# KGGR_MV.net
KiCad netlist of a schematic drawn in EAGLE
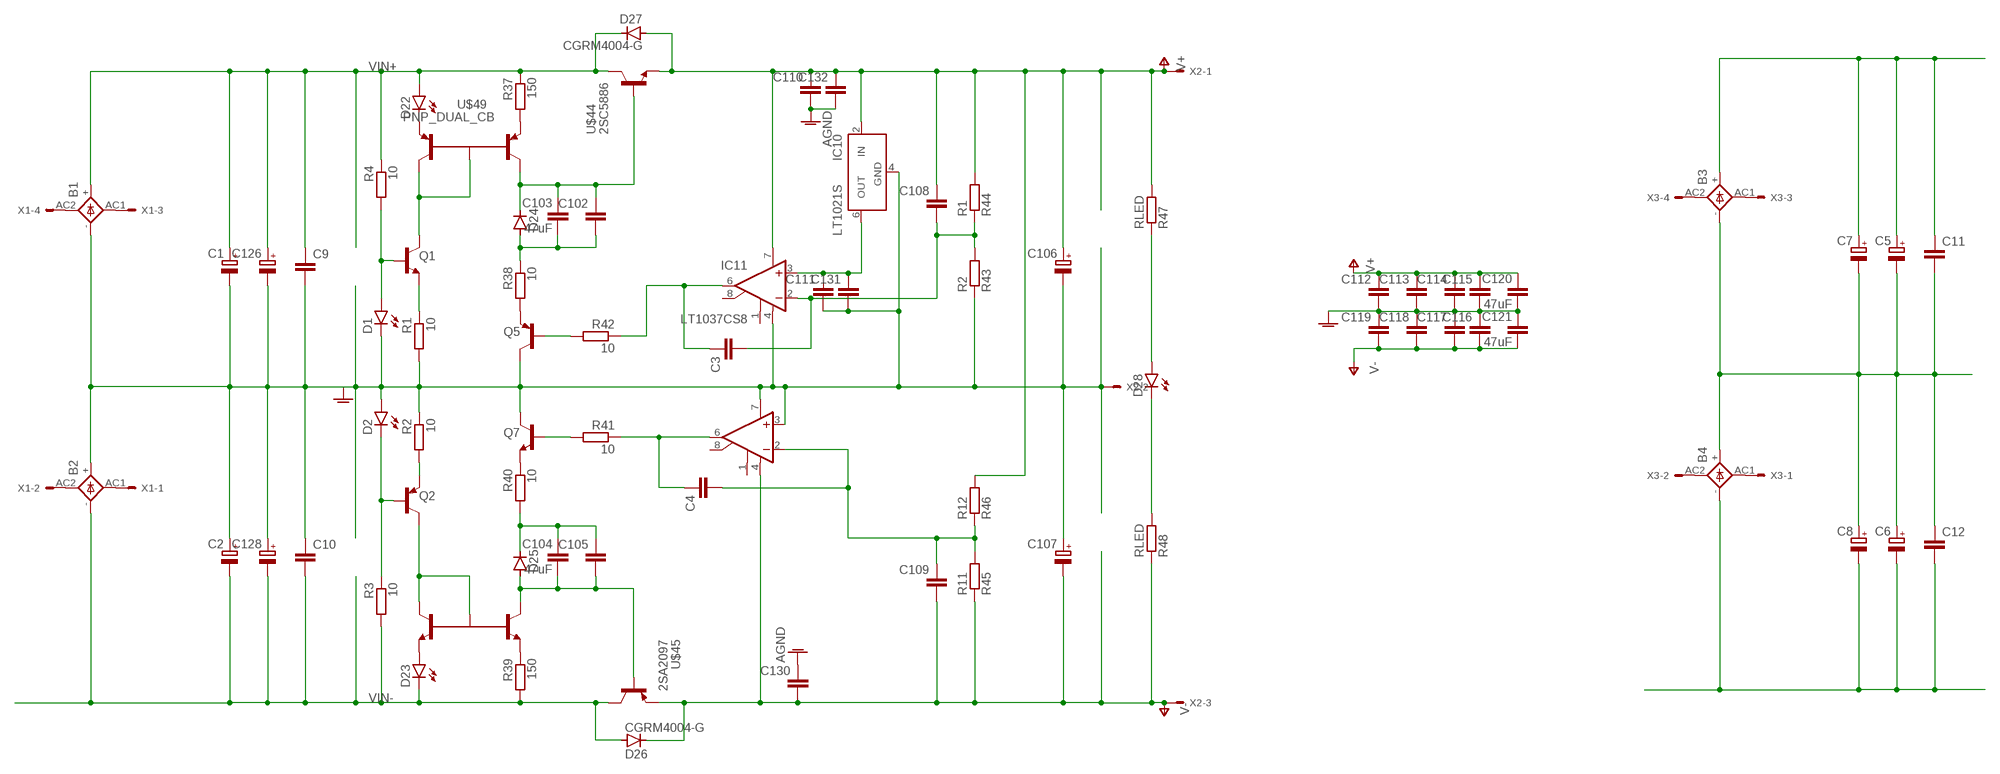
[diagram p0: schematic, sheet 1]

(export (version "E")
  (design (tool "Eeschema 10.0.6"))
  (components
    (comp (ref "B1")
      (value "GBU4")
      (footprint "eagle-import:GBU4S")
      (libsource (lib "eagle-import") (part "GBU4"))
    )
    (comp (ref "B2")
      (value "GBU4")
      (footprint "eagle-import:GBU4S")
      (libsource (lib "eagle-import") (part "GBU4"))
    )
    (comp (ref "B3")
      (value "GBU4")
      (footprint "eagle-import:GBU4S")
      (libsource (lib "eagle-import") (part "GBU4"))
    )
    (comp (ref "B4")
      (value "GBU4")
      (footprint "eagle-import:GBU4S")
      (libsource (lib "eagle-import") (part "GBU4"))
    )
    (comp (ref "C1")
      (value "CPOL-EUE7.5-18")
      (footprint "eagle-import:E7,5-18")
      (libsource (lib "eagle-import") (part "CPOL-EUE7.5-18"))
    )
    (comp (ref "C2")
      (value "CPOL-EUE7.5-18")
      (footprint "eagle-import:E7,5-18")
      (libsource (lib "eagle-import") (part "CPOL-EUE7.5-18"))
    )
    (comp (ref "C3")
      (value "C-EUC0805")
      (footprint "eagle-import:C0805")
      (libsource (lib "eagle-import") (part "C-EUC0805"))
    )
    (comp (ref "C4")
      (value "C-EUC0805")
      (footprint "eagle-import:C0805")
      (libsource (lib "eagle-import") (part "C-EUC0805"))
    )
    (comp (ref "C5")
      (value "CPOL-EUE10-35")
      (footprint "eagle-import:EB35D")
      (libsource (lib "eagle-import") (part "CPOL-EUE10-35"))
    )
    (comp (ref "C6")
      (value "CPOL-EUE10-35")
      (footprint "eagle-import:EB35D")
      (libsource (lib "eagle-import") (part "CPOL-EUE10-35"))
    )
    (comp (ref "C7")
      (value "CPOL-EUE10-35")
      (footprint "eagle-import:EB35D")
      (libsource (lib "eagle-import") (part "CPOL-EUE10-35"))
    )
    (comp (ref "C8")
      (value "CPOL-EUE10-35")
      (footprint "eagle-import:EB35D")
      (libsource (lib "eagle-import") (part "CPOL-EUE10-35"))
    )
    (comp (ref "C9")
      (value "C-EU050-050X075")
      (footprint "eagle-import:C050-050X075")
      (libsource (lib "eagle-import") (part "C-EU050-050X075"))
    )
    (comp (ref "C10")
      (value "C-EU050-050X075")
      (footprint "eagle-import:C050-050X075")
      (libsource (lib "eagle-import") (part "C-EU050-050X075"))
    )
    (comp (ref "C11")
      (value "C-EU050-050X075")
      (footprint "eagle-import:C050-050X075")
      (libsource (lib "eagle-import") (part "C-EU050-050X075"))
    )
    (comp (ref "C12")
      (value "C-EU050-050X075")
      (footprint "eagle-import:C050-050X075")
      (libsource (lib "eagle-import") (part "C-EU050-050X075"))
    )
    (comp (ref "C102")
      (value "C-EUC0805")
      (footprint "eagle-import:C0805")
      (libsource (lib "eagle-import") (part "C-EUC0805"))
    )
    (comp (ref "C103")
      (value "47uF")
      (footprint "eagle-import:C1206")
      (libsource (lib "eagle-import") (part "C-EUC1206"))
    )
    (comp (ref "C104")
      (value "47uF")
      (footprint "eagle-import:C1206")
      (libsource (lib "eagle-import") (part "C-EUC1206"))
    )
    (comp (ref "C105")
      (value "C-EUC0805")
      (footprint "eagle-import:C0805")
      (libsource (lib "eagle-import") (part "C-EUC0805"))
    )
    (comp (ref "C106")
      (value "CPOL-EUE5-10.5")
      (footprint "eagle-import:E5-10,5")
      (libsource (lib "eagle-import") (part "CPOL-EUE5-10.5"))
    )
    (comp (ref "C107")
      (value "CPOL-EUE5-10.5")
      (footprint "eagle-import:E5-10,5")
      (libsource (lib "eagle-import") (part "CPOL-EUE5-10.5"))
    )
    (comp (ref "C108")
      (value "C-EUC0805")
      (footprint "eagle-import:C0805")
      (libsource (lib "eagle-import") (part "C-EUC0805"))
    )
    (comp (ref "C109")
      (value "C-EUC0805")
      (footprint "eagle-import:C0805")
      (libsource (lib "eagle-import") (part "C-EUC0805"))
    )
    (comp (ref "C110")
      (value "C-EUC0805")
      (footprint "eagle-import:C0805")
      (libsource (lib "eagle-import") (part "C-EUC0805"))
    )
    (comp (ref "C111")
      (value "C-EUC0805")
      (footprint "eagle-import:C0805")
      (libsource (lib "eagle-import") (part "C-EUC0805"))
    )
    (comp (ref "C112")
      (value "C-EUC0805")
      (footprint "eagle-import:C0805")
      (libsource (lib "eagle-import") (part "C-EUC0805"))
    )
    (comp (ref "C113")
      (value "C-EUC0805")
      (footprint "eagle-import:C0805")
      (libsource (lib "eagle-import") (part "C-EUC0805"))
    )
    (comp (ref "C114")
      (value "C-EUC0805")
      (footprint "eagle-import:C0805")
      (libsource (lib "eagle-import") (part "C-EUC0805"))
    )
    (comp (ref "C115")
      (value "C-EUC0805")
      (footprint "eagle-import:C0805")
      (libsource (lib "eagle-import") (part "C-EUC0805"))
    )
    (comp (ref "C116")
      (value "C-EUC0805")
      (footprint "eagle-import:C0805")
      (libsource (lib "eagle-import") (part "C-EUC0805"))
    )
    (comp (ref "C117")
      (value "C-EUC0805")
      (footprint "eagle-import:C0805")
      (libsource (lib "eagle-import") (part "C-EUC0805"))
    )
    (comp (ref "C118")
      (value "C-EUC0805")
      (footprint "eagle-import:C0805")
      (libsource (lib "eagle-import") (part "C-EUC0805"))
    )
    (comp (ref "C119")
      (value "C-EUC0805")
      (footprint "eagle-import:C0805")
      (libsource (lib "eagle-import") (part "C-EUC0805"))
    )
    (comp (ref "C120")
      (value "47uF")
      (footprint "eagle-import:C1206")
      (libsource (lib "eagle-import") (part "C-EUC1206"))
    )
    (comp (ref "C121")
      (value "47uF")
      (footprint "eagle-import:C1206")
      (libsource (lib "eagle-import") (part "C-EUC1206"))
    )
    (comp (ref "C126")
      (value "CPOL-EUE7.5-18")
      (footprint "eagle-import:E7,5-18")
      (libsource (lib "eagle-import") (part "CPOL-EUE7.5-18"))
    )
    (comp (ref "C128")
      (value "CPOL-EUE7.5-18")
      (footprint "eagle-import:E7,5-18")
      (libsource (lib "eagle-import") (part "CPOL-EUE7.5-18"))
    )
    (comp (ref "C130")
      (value "C-EUC0805")
      (footprint "eagle-import:C0805")
      (libsource (lib "eagle-import") (part "C-EUC0805"))
    )
    (comp (ref "C131")
      (value "C-EUC0805")
      (footprint "eagle-import:C0805")
      (libsource (lib "eagle-import") (part "C-EUC0805"))
    )
    (comp (ref "C132")
      (value "C-EUC0805")
      (footprint "eagle-import:C0805")
      (libsource (lib "eagle-import") (part "C-EUC0805"))
    )
    (comp (ref "D1")
      (value "LEDVWV1206")
      (footprint "eagle-import:LED_SML1206")
      (libsource (lib "eagle-import") (part "LEDVWV1206"))
    )
    (comp (ref "D2")
      (value "LEDVWV1206")
      (footprint "eagle-import:LED_SML1206")
      (libsource (lib "eagle-import") (part "LEDVWV1206"))
    )
    (comp (ref "D22")
      (value "LEDVWV1206")
      (footprint "eagle-import:LED_SML1206")
      (libsource (lib "eagle-import") (part "LEDVWV1206"))
    )
    (comp (ref "D23")
      (value "LEDVWV1206")
      (footprint "eagle-import:LED_SML1206")
      (libsource (lib "eagle-import") (part "LEDVWV1206"))
    )
    (comp (ref "D24")
      (value "TZMC10")
      (footprint "eagle-import:SOD80C")
      (libsource (lib "eagle-import") (part "DIODE-SOD80C"))
    )
    (comp (ref "D25")
      (value "TZAMC10")
      (footprint "eagle-import:SOD80C")
      (libsource (lib "eagle-import") (part "DIODE-SOD80C"))
    )
    (comp (ref "D26")
      (value "CGRM4004-G")
      (footprint "eagle-import:SOD-123_MINI-SMA")
      (libsource (lib "eagle-import") (part "CGRM400-G4"))
    )
    (comp (ref "D27")
      (value "CGRM4004-G")
      (footprint "eagle-import:SOD-123_MINI-SMA")
      (libsource (lib "eagle-import") (part "CGRM400-G4"))
    )
    (comp (ref "D28")
      (value "LEDVWV1206")
      (footprint "eagle-import:LED_SML1206")
      (libsource (lib "eagle-import") (part "LEDVWV1206"))
    )
    (comp (ref "IC10")
      (value "LT1021S")
      (footprint "eagle-import:SOIC8")
      (fields (field (name "MPN") "LT1021DCS8-10#PBF"))
      (libsource (lib "eagle-import") (part "LT1021S"))
    )
    (comp (ref "IC11")
      (value "LT1037CS8")
      (footprint "eagle-import:SOIC8")
      (libsource (lib "eagle-import") (part "LT10S837C"))
    )
    (comp (ref "IC12")
      (value "LT1037CS8")
      (footprint "eagle-import:SOIC8")
      (libsource (lib "eagle-import") (part "LT10S837C"))
    )
    (comp (ref "Q1")
      (value "TRANSISTOR_BC847CLT1-NPN-SOT23-BEC")
      (footprint "eagle-import:TRANSISTOR_SOT23-BEC")
      (libsource (lib "eagle-import") (part "TRANSISTOR_-NPN-SOT23-BECBC847CLT1"))
    )
    (comp (ref "Q2")
      (value "TRANSISTOR_BC857C-PNP-SOT23-BEC")
      (footprint "eagle-import:TRANSISTOR_SOT23-BEC")
      (libsource (lib "eagle-import") (part "TRANSISTOR_-PNP-SOT23-BECBC857C"))
    )
    (comp (ref "Q5")
      (value "TRANSISTOR_BC857C-PNP-SOT23-BEC")
      (footprint "eagle-import:TRANSISTOR_SOT23-BEC")
      (libsource (lib "eagle-import") (part "TRANSISTOR_-PNP-SOT23-BECBC857C"))
    )
    (comp (ref "Q7")
      (value "TRANSISTOR_BC847CLT1-NPN-SOT23-BEC")
      (footprint "eagle-import:TRANSISTOR_SOT23-BEC")
      (libsource (lib "eagle-import") (part "TRANSISTOR_-NPN-SOT23-BECBC847CLT1"))
    )
    (comp (ref "R1")
      (value "10")
      (footprint "eagle-import:MINI_MELF-0204W")
      (libsource (lib "eagle-import") (part "R-EU_MELF0204W"))
    )
    (comp (ref "R2")
      (value "10")
      (footprint "eagle-import:MINI_MELF-0204W")
      (libsource (lib "eagle-import") (part "R-EU_MELF0204W"))
    )
    (comp (ref "R3")
      (value "10")
      (footprint "eagle-import:MINI_MELF-0204W")
      (libsource (lib "eagle-import") (part "R-EU_MELF0204W"))
    )
    (comp (ref "R4")
      (value "10")
      (footprint "eagle-import:MINI_MELF-0204W")
      (libsource (lib "eagle-import") (part "R-EU_MELF0204W"))
    )
    (comp (ref "R37")
      (value "150")
      (footprint "eagle-import:MINI_MELF-0204W")
      (libsource (lib "eagle-import") (part "R-EU_MELF0204W"))
    )
    (comp (ref "R38")
      (value "10")
      (footprint "eagle-import:MINI_MELF-0204W")
      (libsource (lib "eagle-import") (part "R-EU_MELF0204W"))
    )
    (comp (ref "R39")
      (value "150")
      (footprint "eagle-import:MINI_MELF-0204W")
      (libsource (lib "eagle-import") (part "R-EU_MELF0204W"))
    )
    (comp (ref "R40")
      (value "10")
      (footprint "eagle-import:MINI_MELF-0204W")
      (libsource (lib "eagle-import") (part "R-EU_MELF0204W"))
    )
    (comp (ref "R41")
      (value "10")
      (footprint "eagle-import:MINI_MELF-0204W")
      (libsource (lib "eagle-import") (part "R-EU_MELF0204W"))
    )
    (comp (ref "R42")
      (value "10")
      (footprint "eagle-import:MINI_MELF-0204W")
      (libsource (lib "eagle-import") (part "R-EU_MELF0204W"))
    )
    (comp (ref "R43")
      (value "R2")
      (footprint "eagle-import:MINI_MELF-0204W")
      (libsource (lib "eagle-import") (part "R-EU_MELF0204W"))
    )
    (comp (ref "R44")
      (value "R1")
      (footprint "eagle-import:MINI_MELF-0204W")
      (libsource (lib "eagle-import") (part "R-EU_MELF0204W"))
    )
    (comp (ref "R45")
      (value "R11")
      (footprint "eagle-import:MINI_MELF-0204W")
      (libsource (lib "eagle-import") (part "R-EU_MELF0204W"))
    )
    (comp (ref "R46")
      (value "R12")
      (footprint "eagle-import:MINI_MELF-0204W")
      (libsource (lib "eagle-import") (part "R-EU_MELF0204W"))
    )
    (comp (ref "R47")
      (value "RLED")
      (footprint "eagle-import:MINI_MELF-0204W")
      (libsource (lib "eagle-import") (part "R-EU_MELF0204W"))
    )
    (comp (ref "R48")
      (value "RLED")
      (footprint "eagle-import:MINI_MELF-0204W")
      (libsource (lib "eagle-import") (part "R-EU_MELF0204W"))
    )
    (comp (ref "U$44")
      (value "2SC5886")
      (footprint "eagle-import:NEW-PWMOLD")
      (libsource (lib "eagle-import") (part "2SC5886"))
    )
    (comp (ref "U$45")
      (value "2SA2097")
      (footprint "eagle-import:NEW-PWMOLD")
      (libsource (lib "eagle-import") (part "2SA2097"))
    )
    (comp (ref "U$48")
      (value "NPN_DUAL_CBSOT-25-5")
      (footprint "eagle-import:SOT25")
      (libsource (lib "eagle-import") (part "NPN_DUAL_CBSOT-25-5"))
    )
    (comp (ref "U$49")
      (value "PNP_DUAL_CB")
      (footprint "eagle-import:SOT25")
      (libsource (lib "eagle-import") (part "PNP_DUAL_CB"))
    )
    (comp (ref "X1")
      (value "KK-156-4")
      (footprint "eagle-import:KK-156-4")
      (fields (field (name "MF") "MOLEX"))
      (libsource (lib "eagle-import") (part "KK-156-4"))
    )
    (comp (ref "X2")
      (value "KK-156-3")
      (footprint "eagle-import:KK-156-3")
      (fields (field (name "MF") "MOLEX"))
      (libsource (lib "eagle-import") (part "KK-156-3"))
    )
    (comp (ref "X3")
      (value "KK-156-4")
      (footprint "eagle-import:KK-156-4")
      (fields (field (name "MF") "MOLEX"))
      (libsource (lib "eagle-import") (part "KK-156-4"))
    )
  )
  (nets
    (net (code "1") (name "/VIN+") (class "Default")
      (node (ref "B1") (pin "+") (pinfunction "+_+") (pintype "passive"))
      (node (ref "C1") (pin "+") (pinfunction "+_+") (pintype "passive"))
      (node (ref "C126") (pin "+") (pinfunction "+_+") (pintype "passive"))
      (node (ref "C9") (pin "1") (pinfunction "1_1") (pintype "passive"))
      (node (ref "D22") (pin "A") (pinfunction "A_A") (pintype "passive"))
      (node (ref "D27") (pin "C") (pinfunction "C_C") (pintype "passive"))
      (node (ref "R37") (pin "1") (pinfunction "1_1") (pintype "passive"))
      (node (ref "R4") (pin "1") (pinfunction "1_1") (pintype "passive"))
      (node (ref "U$44") (pin "2") (pinfunction "C_2") (pintype "passive"))
      (node (ref "U$44") (pin "4") (pinfunction "C_4") (pintype "passive"))
      (node (ref "U$44") (pin "P$1") (pinfunction "C_P$1") (pintype "passive"))
      (node (ref "U$44") (pin "P$10") (pinfunction "C_P$10") (pintype "passive"))
      (node (ref "U$44") (pin "P$11") (pinfunction "C_P$11") (pintype "passive"))
      (node (ref "U$44") (pin "P$12") (pinfunction "C_P$12") (pintype "passive"))
      (node (ref "U$44") (pin "P$13") (pinfunction "C_P$13") (pintype "passive"))
      (node (ref "U$44") (pin "P$14") (pinfunction "C_P$14") (pintype "passive"))
      (node (ref "U$44") (pin "P$15") (pinfunction "C_P$15") (pintype "passive"))
      (node (ref "U$44") (pin "P$16") (pinfunction "C_P$16") (pintype "passive"))
      (node (ref "U$44") (pin "P$17") (pinfunction "C_P$17") (pintype "passive"))
      (node (ref "U$44") (pin "P$18") (pinfunction "C_P$18") (pintype "passive"))
      (node (ref "U$44") (pin "P$19") (pinfunction "C_P$19") (pintype "passive"))
      (node (ref "U$44") (pin "P$2") (pinfunction "C_P$2") (pintype "passive"))
      (node (ref "U$44") (pin "P$20") (pinfunction "C_P$20") (pintype "passive"))
      (node (ref "U$44") (pin "P$21") (pinfunction "C_P$21") (pintype "passive"))
      (node (ref "U$44") (pin "P$22") (pinfunction "C_P$22") (pintype "passive"))
      (node (ref "U$44") (pin "P$23") (pinfunction "C_P$23") (pintype "passive"))
      (node (ref "U$44") (pin "P$24") (pinfunction "C_P$24") (pintype "passive"))
      (node (ref "U$44") (pin "P$25") (pinfunction "C_P$25") (pintype "passive"))
      (node (ref "U$44") (pin "P$26") (pinfunction "C_P$26") (pintype "passive"))
      (node (ref "U$44") (pin "P$27") (pinfunction "C_P$27") (pintype "passive"))
      (node (ref "U$44") (pin "P$28") (pinfunction "C_P$28") (pintype "passive"))
      (node (ref "U$44") (pin "P$29") (pinfunction "C_P$29") (pintype "passive"))
      (node (ref "U$44") (pin "P$3") (pinfunction "C_P$3") (pintype "passive"))
      (node (ref "U$44") (pin "P$30") (pinfunction "C_P$30") (pintype "passive"))
      (node (ref "U$44") (pin "P$31") (pinfunction "C_P$31") (pintype "passive"))
      (node (ref "U$44") (pin "P$32") (pinfunction "C_P$32") (pintype "passive"))
      (node (ref "U$44") (pin "P$33") (pinfunction "C_P$33") (pintype "passive"))
      (node (ref "U$44") (pin "P$34") (pinfunction "C_P$34") (pintype "passive"))
      (node (ref "U$44") (pin "P$35") (pinfunction "C_P$35") (pintype "passive"))
      (node (ref "U$44") (pin "P$36") (pinfunction "C_P$36") (pintype "passive"))
      (node (ref "U$44") (pin "P$37") (pinfunction "C_P$37") (pintype "passive"))
      (node (ref "U$44") (pin "P$38") (pinfunction "C_P$38") (pintype "passive"))
      (node (ref "U$44") (pin "P$39") (pinfunction "C_P$39") (pintype "passive"))
      (node (ref "U$44") (pin "P$4") (pinfunction "C_P$4") (pintype "passive"))
      (node (ref "U$44") (pin "P$40") (pinfunction "C_P$40") (pintype "passive"))
      (node (ref "U$44") (pin "P$41") (pinfunction "C_P$41") (pintype "passive"))
      (node (ref "U$44") (pin "P$42") (pinfunction "C_P$42") (pintype "passive"))
      (node (ref "U$44") (pin "P$43") (pinfunction "C_P$43") (pintype "passive"))
      (node (ref "U$44") (pin "P$44") (pinfunction "C_P$44") (pintype "passive"))
      (node (ref "U$44") (pin "P$45") (pinfunction "C_P$45") (pintype "passive"))
      (node (ref "U$44") (pin "P$46") (pinfunction "C_P$46") (pintype "passive"))
      (node (ref "U$44") (pin "P$47") (pinfunction "C_P$47") (pintype "passive"))
      (node (ref "U$44") (pin "P$48") (pinfunction "C_P$48") (pintype "passive"))
      (node (ref "U$44") (pin "P$49") (pinfunction "C_P$49") (pintype "passive"))
      (node (ref "U$44") (pin "P$5") (pinfunction "C_P$5") (pintype "passive"))
      (node (ref "U$44") (pin "P$50") (pinfunction "C_P$50") (pintype "passive"))
      (node (ref "U$44") (pin "P$51") (pinfunction "C_P$51") (pintype "passive"))
      (node (ref "U$44") (pin "P$52") (pinfunction "C_P$52") (pintype "passive"))
      (node (ref "U$44") (pin "P$53") (pinfunction "C_P$53") (pintype "passive"))
      (node (ref "U$44") (pin "P$54") (pinfunction "C_P$54") (pintype "passive"))
      (node (ref "U$44") (pin "P$55") (pinfunction "C_P$55") (pintype "passive"))
      (node (ref "U$44") (pin "P$56") (pinfunction "C_P$56") (pintype "passive"))
      (node (ref "U$44") (pin "P$57") (pinfunction "C_P$57") (pintype "passive"))
      (node (ref "U$44") (pin "P$58") (pinfunction "C_P$58") (pintype "passive"))
      (node (ref "U$44") (pin "P$59") (pinfunction "C_P$59") (pintype "passive"))
      (node (ref "U$44") (pin "P$6") (pinfunction "C_P$6") (pintype "passive"))
      (node (ref "U$44") (pin "P$60") (pinfunction "C_P$60") (pintype "passive"))
      (node (ref "U$44") (pin "P$61") (pinfunction "C_P$61") (pintype "passive"))
      (node (ref "U$44") (pin "P$62") (pinfunction "C_P$62") (pintype "passive"))
      (node (ref "U$44") (pin "P$63") (pinfunction "C_P$63") (pintype "passive"))
      (node (ref "U$44") (pin "P$7") (pinfunction "C_P$7") (pintype "passive"))
      (node (ref "U$44") (pin "P$8") (pinfunction "C_P$8") (pintype "passive"))
      (node (ref "U$44") (pin "P$9") (pinfunction "C_P$9") (pintype "passive"))
    )
    (net (code "2") (name "/VIN-") (class "Default")
      (node (ref "B2") (pin "-") (pinfunction "-_-") (pintype "passive"))
      (node (ref "C10") (pin "2") (pinfunction "2_2") (pintype "passive"))
      (node (ref "C128") (pin "-") (pinfunction "-_-") (pintype "passive"))
      (node (ref "C2") (pin "-") (pinfunction "-_-") (pintype "passive"))
      (node (ref "D23") (pin "C") (pinfunction "C_C") (pintype "passive"))
      (node (ref "D26") (pin "A") (pinfunction "A_A") (pintype "passive"))
      (node (ref "R3") (pin "2") (pinfunction "2_2") (pintype "passive"))
      (node (ref "R39") (pin "2") (pinfunction "2_2") (pintype "passive"))
      (node (ref "U$45") (pin "2") (pinfunction "C_2") (pintype "passive"))
      (node (ref "U$45") (pin "4") (pinfunction "C_4") (pintype "passive"))
      (node (ref "U$45") (pin "P$1") (pinfunction "C_P$1") (pintype "passive"))
      (node (ref "U$45") (pin "P$10") (pinfunction "C_P$10") (pintype "passive"))
      (node (ref "U$45") (pin "P$11") (pinfunction "C_P$11") (pintype "passive"))
      (node (ref "U$45") (pin "P$12") (pinfunction "C_P$12") (pintype "passive"))
      (node (ref "U$45") (pin "P$13") (pinfunction "C_P$13") (pintype "passive"))
      (node (ref "U$45") (pin "P$14") (pinfunction "C_P$14") (pintype "passive"))
      (node (ref "U$45") (pin "P$15") (pinfunction "C_P$15") (pintype "passive"))
      (node (ref "U$45") (pin "P$16") (pinfunction "C_P$16") (pintype "passive"))
      (node (ref "U$45") (pin "P$17") (pinfunction "C_P$17") (pintype "passive"))
      (node (ref "U$45") (pin "P$18") (pinfunction "C_P$18") (pintype "passive"))
      (node (ref "U$45") (pin "P$19") (pinfunction "C_P$19") (pintype "passive"))
      (node (ref "U$45") (pin "P$2") (pinfunction "C_P$2") (pintype "passive"))
      (node (ref "U$45") (pin "P$20") (pinfunction "C_P$20") (pintype "passive"))
      (node (ref "U$45") (pin "P$21") (pinfunction "C_P$21") (pintype "passive"))
      (node (ref "U$45") (pin "P$22") (pinfunction "C_P$22") (pintype "passive"))
      (node (ref "U$45") (pin "P$23") (pinfunction "C_P$23") (pintype "passive"))
      (node (ref "U$45") (pin "P$24") (pinfunction "C_P$24") (pintype "passive"))
      (node (ref "U$45") (pin "P$25") (pinfunction "C_P$25") (pintype "passive"))
      (node (ref "U$45") (pin "P$26") (pinfunction "C_P$26") (pintype "passive"))
      (node (ref "U$45") (pin "P$27") (pinfunction "C_P$27") (pintype "passive"))
      (node (ref "U$45") (pin "P$28") (pinfunction "C_P$28") (pintype "passive"))
      (node (ref "U$45") (pin "P$29") (pinfunction "C_P$29") (pintype "passive"))
      (node (ref "U$45") (pin "P$3") (pinfunction "C_P$3") (pintype "passive"))
      (node (ref "U$45") (pin "P$30") (pinfunction "C_P$30") (pintype "passive"))
      (node (ref "U$45") (pin "P$31") (pinfunction "C_P$31") (pintype "passive"))
      (node (ref "U$45") (pin "P$32") (pinfunction "C_P$32") (pintype "passive"))
      (node (ref "U$45") (pin "P$33") (pinfunction "C_P$33") (pintype "passive"))
      (node (ref "U$45") (pin "P$34") (pinfunction "C_P$34") (pintype "passive"))
      (node (ref "U$45") (pin "P$35") (pinfunction "C_P$35") (pintype "passive"))
      (node (ref "U$45") (pin "P$36") (pinfunction "C_P$36") (pintype "passive"))
      (node (ref "U$45") (pin "P$37") (pinfunction "C_P$37") (pintype "passive"))
      (node (ref "U$45") (pin "P$38") (pinfunction "C_P$38") (pintype "passive"))
      (node (ref "U$45") (pin "P$39") (pinfunction "C_P$39") (pintype "passive"))
      (node (ref "U$45") (pin "P$4") (pinfunction "C_P$4") (pintype "passive"))
      (node (ref "U$45") (pin "P$40") (pinfunction "C_P$40") (pintype "passive"))
      (node (ref "U$45") (pin "P$41") (pinfunction "C_P$41") (pintype "passive"))
      (node (ref "U$45") (pin "P$42") (pinfunction "C_P$42") (pintype "passive"))
      (node (ref "U$45") (pin "P$43") (pinfunction "C_P$43") (pintype "passive"))
      (node (ref "U$45") (pin "P$44") (pinfunction "C_P$44") (pintype "passive"))
      (node (ref "U$45") (pin "P$45") (pinfunction "C_P$45") (pintype "passive"))
      (node (ref "U$45") (pin "P$46") (pinfunction "C_P$46") (pintype "passive"))
      (node (ref "U$45") (pin "P$47") (pinfunction "C_P$47") (pintype "passive"))
      (node (ref "U$45") (pin "P$48") (pinfunction "C_P$48") (pintype "passive"))
      (node (ref "U$45") (pin "P$49") (pinfunction "C_P$49") (pintype "passive"))
      (node (ref "U$45") (pin "P$5") (pinfunction "C_P$5") (pintype "passive"))
      (node (ref "U$45") (pin "P$50") (pinfunction "C_P$50") (pintype "passive"))
      (node (ref "U$45") (pin "P$51") (pinfunction "C_P$51") (pintype "passive"))
      (node (ref "U$45") (pin "P$52") (pinfunction "C_P$52") (pintype "passive"))
      (node (ref "U$45") (pin "P$53") (pinfunction "C_P$53") (pintype "passive"))
      (node (ref "U$45") (pin "P$54") (pinfunction "C_P$54") (pintype "passive"))
      (node (ref "U$45") (pin "P$55") (pinfunction "C_P$55") (pintype "passive"))
      (node (ref "U$45") (pin "P$56") (pinfunction "C_P$56") (pintype "passive"))
      (node (ref "U$45") (pin "P$57") (pinfunction "C_P$57") (pintype "passive"))
      (node (ref "U$45") (pin "P$58") (pinfunction "C_P$58") (pintype "passive"))
      (node (ref "U$45") (pin "P$59") (pinfunction "C_P$59") (pintype "passive"))
      (node (ref "U$45") (pin "P$6") (pinfunction "C_P$6") (pintype "passive"))
      (node (ref "U$45") (pin "P$60") (pinfunction "C_P$60") (pintype "passive"))
      (node (ref "U$45") (pin "P$61") (pinfunction "C_P$61") (pintype "passive"))
      (node (ref "U$45") (pin "P$62") (pinfunction "C_P$62") (pintype "passive"))
      (node (ref "U$45") (pin "P$63") (pinfunction "C_P$63") (pintype "passive"))
      (node (ref "U$45") (pin "P$7") (pinfunction "C_P$7") (pintype "passive"))
      (node (ref "U$45") (pin "P$8") (pinfunction "C_P$8") (pintype "passive"))
      (node (ref "U$45") (pin "P$9") (pinfunction "C_P$9") (pintype "passive"))
    )
    (net (code "3") (name "AGND") (class "Default")
      (node (ref "B1") (pin "-") (pinfunction "-_-") (pintype "passive"))
      (node (ref "B2") (pin "+") (pinfunction "+_+") (pintype "passive"))
      (node (ref "C1") (pin "-") (pinfunction "-_-") (pintype "passive"))
      (node (ref "C10") (pin "1") (pinfunction "1_1") (pintype "passive"))
      (node (ref "C106") (pin "-") (pinfunction "-_-") (pintype "passive"))
      (node (ref "C107") (pin "+") (pinfunction "+_+") (pintype "passive"))
      (node (ref "C110") (pin "2") (pinfunction "2_2") (pintype "passive"))
      (node (ref "C111") (pin "2") (pinfunction "2_2") (pintype "passive"))
      (node (ref "C112") (pin "2") (pinfunction "2_2") (pintype "passive"))
      (node (ref "C113") (pin "2") (pinfunction "2_2") (pintype "passive"))
      (node (ref "C114") (pin "2") (pinfunction "2_2") (pintype "passive"))
      (node (ref "C115") (pin "2") (pinfunction "2_2") (pintype "passive"))
      (node (ref "C116") (pin "1") (pinfunction "1_1") (pintype "passive"))
      (node (ref "C117") (pin "1") (pinfunction "1_1") (pintype "passive"))
      (node (ref "C118") (pin "1") (pinfunction "1_1") (pintype "passive"))
      (node (ref "C119") (pin "1") (pinfunction "1_1") (pintype "passive"))
      (node (ref "C120") (pin "2") (pinfunction "2_2") (pintype "passive"))
      (node (ref "C121") (pin "1") (pinfunction "1_1") (pintype "passive"))
      (node (ref "C126") (pin "-") (pinfunction "-_-") (pintype "passive"))
      (node (ref "C128") (pin "+") (pinfunction "+_+") (pintype "passive"))
      (node (ref "C130") (pin "1") (pinfunction "1_1") (pintype "passive"))
      (node (ref "C131") (pin "2") (pinfunction "2_2") (pintype "passive"))
      (node (ref "C132") (pin "2") (pinfunction "2_2") (pintype "passive"))
      (node (ref "C2") (pin "+") (pinfunction "+_+") (pintype "passive"))
      (node (ref "C9") (pin "2") (pinfunction "2_2") (pintype "passive"))
      (node (ref "D1") (pin "C") (pinfunction "C_C") (pintype "passive"))
      (node (ref "D2") (pin "A") (pinfunction "A_A") (pintype "passive"))
      (node (ref "IC10") (pin "4") (pinfunction "GND_4") (pintype "power_in"))
      (node (ref "IC11") (pin "4") (pinfunction "V-_4") (pintype "power_in"))
      (node (ref "IC12") (pin "3") (pinfunction "+IN_3") (pintype "input"))
      (node (ref "IC12") (pin "7") (pinfunction "V+_7") (pintype "power_in"))
      (node (ref "Q5") (pin "C") (pinfunction "C_C") (pintype "passive"))
      (node (ref "Q7") (pin "C") (pinfunction "C_C") (pintype "passive"))
      (node (ref "R1") (pin "2") (pinfunction "2_2") (pintype "passive"))
      (node (ref "R2") (pin "1") (pinfunction "1_1") (pintype "passive"))
      (node (ref "R43") (pin "1") (pinfunction "1_1") (pintype "passive"))
      (node (ref "X2") (pin "2") (pinfunction "S_2") (pintype "passive"))
    )
    (net (code "4") (name "Net-(B1-AC1)") (class "Default")
      (node (ref "B1") (pin "AC2") (pinfunction "AC1_AC2") (pintype "passive"))
      (node (ref "X1") (pin "4") (pinfunction "S_4") (pintype "passive"))
    )
    (net (code "5") (name "Net-(B1-AC2)") (class "Default")
      (node (ref "B1") (pin "AC1") (pinfunction "AC2_AC1") (pintype "passive"))
      (node (ref "X1") (pin "3") (pinfunction "S_3") (pintype "passive"))
    )
    (net (code "6") (name "Net-(B2-AC1)") (class "Default")
      (node (ref "B2") (pin "AC2") (pinfunction "AC1_AC2") (pintype "passive"))
      (node (ref "X1") (pin "2") (pinfunction "S_2") (pintype "passive"))
    )
    (net (code "7") (name "Net-(B2-AC2)") (class "Default")
      (node (ref "B2") (pin "AC1") (pinfunction "AC2_AC1") (pintype "passive"))
      (node (ref "X1") (pin "1") (pinfunction "S_1") (pintype "passive"))
    )
    (net (code "8") (name "Net-(B3-AC1)") (class "Default")
      (node (ref "B3") (pin "AC2") (pinfunction "AC1_AC2") (pintype "passive"))
      (node (ref "X3") (pin "4") (pinfunction "S_4") (pintype "passive"))
    )
    (net (code "9") (name "Net-(B3-AC2)") (class "Default")
      (node (ref "B3") (pin "AC1") (pinfunction "AC2_AC1") (pintype "passive"))
      (node (ref "X3") (pin "3") (pinfunction "S_3") (pintype "passive"))
    )
    (net (code "10") (name "Net-(B3-Pad+)") (class "Default")
      (node (ref "B3") (pin "+") (pinfunction "+_+") (pintype "passive"))
      (node (ref "C11") (pin "1") (pinfunction "1_1") (pintype "passive"))
      (node (ref "C5") (pin "+") (pinfunction "+_+") (pintype "passive"))
      (node (ref "C7") (pin "+") (pinfunction "+_+") (pintype "passive"))
    )
    (net (code "11") (name "Net-(B3-Pad-)") (class "Default")
      (node (ref "B3") (pin "-") (pinfunction "-_-") (pintype "passive"))
      (node (ref "B4") (pin "+") (pinfunction "+_+") (pintype "passive"))
      (node (ref "C11") (pin "2") (pinfunction "2_2") (pintype "passive"))
      (node (ref "C12") (pin "1") (pinfunction "1_1") (pintype "passive"))
      (node (ref "C5") (pin "-") (pinfunction "-_-") (pintype "passive"))
      (node (ref "C6") (pin "+") (pinfunction "+_+") (pintype "passive"))
      (node (ref "C7") (pin "-") (pinfunction "-_-") (pintype "passive"))
      (node (ref "C8") (pin "+") (pinfunction "+_+") (pintype "passive"))
    )
    (net (code "12") (name "Net-(B4-AC1)") (class "Default")
      (node (ref "B4") (pin "AC2") (pinfunction "AC1_AC2") (pintype "passive"))
      (node (ref "X3") (pin "2") (pinfunction "S_2") (pintype "passive"))
    )
    (net (code "13") (name "Net-(B4-AC2)") (class "Default")
      (node (ref "B4") (pin "AC1") (pinfunction "AC2_AC1") (pintype "passive"))
      (node (ref "X3") (pin "1") (pinfunction "S_1") (pintype "passive"))
    )
    (net (code "14") (name "Net-(B4-Pad-)") (class "Default")
      (node (ref "B4") (pin "-") (pinfunction "-_-") (pintype "passive"))
      (node (ref "C12") (pin "2") (pinfunction "2_2") (pintype "passive"))
      (node (ref "C6") (pin "-") (pinfunction "-_-") (pintype "passive"))
      (node (ref "C8") (pin "-") (pinfunction "-_-") (pintype "passive"))
    )
    (net (code "15") (name "Net-(C102-Pad2)") (class "Default")
      (node (ref "C102") (pin "2") (pinfunction "2_2") (pintype "passive"))
      (node (ref "C103") (pin "2") (pinfunction "2_2") (pintype "passive"))
      (node (ref "D24") (pin "A") (pinfunction "A_A") (pintype "passive"))
      (node (ref "R38") (pin "1") (pinfunction "1_1") (pintype "passive"))
    )
    (net (code "16") (name "Net-(C104-Pad1)") (class "Default")
      (node (ref "C104") (pin "1") (pinfunction "1_1") (pintype "passive"))
      (node (ref "C105") (pin "1") (pinfunction "1_1") (pintype "passive"))
      (node (ref "D25") (pin "C") (pinfunction "C_C") (pintype "passive"))
      (node (ref "R40") (pin "2") (pinfunction "2_2") (pintype "passive"))
    )
    (net (code "17") (name "Net-(D1-PadA)") (class "Default")
      (node (ref "D1") (pin "A") (pinfunction "A_A") (pintype "passive"))
      (node (ref "Q1") (pin "B") (pinfunction "B_B") (pintype "passive"))
      (node (ref "R4") (pin "2") (pinfunction "2_2") (pintype "passive"))
    )
    (net (code "18") (name "Net-(D2-PadC)") (class "Default")
      (node (ref "D2") (pin "C") (pinfunction "C_C") (pintype "passive"))
      (node (ref "Q2") (pin "B") (pinfunction "B_B") (pintype "passive"))
      (node (ref "R3") (pin "1") (pinfunction "1_1") (pintype "passive"))
    )
    (net (code "19") (name "Net-(D28-PadA)") (class "Default")
      (node (ref "D28") (pin "A") (pinfunction "A_A") (pintype "passive"))
      (node (ref "R47") (pin "1") (pinfunction "1_1") (pintype "passive"))
    )
    (net (code "20") (name "Net-(D28-PadC)") (class "Default")
      (node (ref "D28") (pin "C") (pinfunction "C_C") (pintype "passive"))
      (node (ref "R48") (pin "2") (pinfunction "2_2") (pintype "passive"))
    )
    (net (code "21") (name "Net-(IC10-OUT)") (class "Default")
      (node (ref "C111") (pin "1") (pinfunction "1_1") (pintype "passive"))
      (node (ref "C131") (pin "1") (pinfunction "1_1") (pintype "passive"))
      (node (ref "IC10") (pin "6") (pinfunction "OUT_6") (pintype "output"))
      (node (ref "IC11") (pin "3") (pinfunction "+IN_3") (pintype "input"))
    )
    (net (code "22") (name "Net-(IC11--IN)") (class "Default")
      (node (ref "C108") (pin "2") (pinfunction "2_2") (pintype "passive"))
      (node (ref "C3") (pin "2") (pinfunction "2_2") (pintype "passive"))
      (node (ref "IC11") (pin "2") (pinfunction "-IN_2") (pintype "input"))
      (node (ref "R43") (pin "2") (pinfunction "2_2") (pintype "passive"))
      (node (ref "R44") (pin "1") (pinfunction "1_1") (pintype "passive"))
    )
    (net (code "23") (name "Net-(IC11-OUT)") (class "Default")
      (node (ref "C3") (pin "1") (pinfunction "1_1") (pintype "passive"))
      (node (ref "IC11") (pin "6") (pinfunction "OUT_6") (pintype "output"))
      (node (ref "R42") (pin "1") (pinfunction "1_1") (pintype "passive"))
    )
    (net (code "24") (name "Net-(IC12--IN)") (class "Default")
      (node (ref "C109") (pin "1") (pinfunction "1_1") (pintype "passive"))
      (node (ref "C4") (pin "2") (pinfunction "2_2") (pintype "passive"))
      (node (ref "IC12") (pin "2") (pinfunction "-IN_2") (pintype "input"))
      (node (ref "R45") (pin "2") (pinfunction "2_2") (pintype "passive"))
      (node (ref "R46") (pin "1") (pinfunction "1_1") (pintype "passive"))
    )
    (net (code "25") (name "Net-(IC12-OUT)") (class "Default")
      (node (ref "C4") (pin "1") (pinfunction "1_1") (pintype "passive"))
      (node (ref "IC12") (pin "6") (pinfunction "OUT_6") (pintype "output"))
      (node (ref "R41") (pin "1") (pinfunction "1_1") (pintype "passive"))
    )
    (net (code "26") (name "Net-(Q1-PadE)") (class "Default")
      (node (ref "Q1") (pin "E") (pinfunction "E_E") (pintype "passive"))
      (node (ref "R1") (pin "1") (pinfunction "1_1") (pintype "passive"))
    )
    (net (code "27") (name "Net-(Q2-PadE)") (class "Default")
      (node (ref "Q2") (pin "E") (pinfunction "E_E") (pintype "passive"))
      (node (ref "R2") (pin "2") (pinfunction "2_2") (pintype "passive"))
    )
    (net (code "28") (name "Net-(Q5-PadB)") (class "Default")
      (node (ref "Q5") (pin "B") (pinfunction "B_B") (pintype "passive"))
      (node (ref "R42") (pin "2") (pinfunction "2_2") (pintype "passive"))
    )
    (net (code "29") (name "Net-(Q5-PadE)") (class "Default")
      (node (ref "Q5") (pin "E") (pinfunction "E_E") (pintype "passive"))
      (node (ref "R38") (pin "2") (pinfunction "2_2") (pintype "passive"))
    )
    (net (code "30") (name "Net-(Q7-PadB)") (class "Default")
      (node (ref "Q7") (pin "B") (pinfunction "B_B") (pintype "passive"))
      (node (ref "R41") (pin "2") (pinfunction "2_2") (pintype "passive"))
    )
    (net (code "31") (name "Net-(Q7-PadE)") (class "Default")
      (node (ref "Q7") (pin "E") (pinfunction "E_E") (pintype "passive"))
      (node (ref "R40") (pin "1") (pinfunction "1_1") (pintype "passive"))
    )
    (net (code "32") (name "Net-(U$44-B)") (class "Default")
      (node (ref "C102") (pin "1") (pinfunction "1_1") (pintype "passive"))
      (node (ref "C103") (pin "1") (pinfunction "1_1") (pintype "passive"))
      (node (ref "D24") (pin "C") (pinfunction "C_C") (pintype "passive"))
      (node (ref "U$44") (pin "1") (pinfunction "B_1") (pintype "passive"))
      (node (ref "U$49") (pin "4") (pinfunction "C2_4") (pintype "passive"))
    )
    (net (code "33") (name "Net-(U$45-B)") (class "Default")
      (node (ref "C104") (pin "2") (pinfunction "2_2") (pintype "passive"))
      (node (ref "C105") (pin "2") (pinfunction "2_2") (pintype "passive"))
      (node (ref "D25") (pin "A") (pinfunction "A_A") (pintype "passive"))
      (node (ref "U$45") (pin "1") (pinfunction "B_1") (pintype "passive"))
      (node (ref "U$48") (pin "4") (pinfunction "C2_4") (pintype "passive"))
    )
    (net (code "34") (name "Net-(U$48-B)") (class "Default")
      (node (ref "Q2") (pin "C") (pinfunction "C_C") (pintype "passive"))
      (node (ref "U$48") (pin "2") (pinfunction "B_2") (pintype "passive"))
      (node (ref "U$48") (pin "5") (pinfunction "C1_5") (pintype "passive"))
    )
    (net (code "35") (name "Net-(U$48-E1)") (class "Default")
      (node (ref "D23") (pin "A") (pinfunction "A_A") (pintype "passive"))
      (node (ref "U$48") (pin "1") (pinfunction "E1_1") (pintype "passive"))
    )
    (net (code "36") (name "Net-(U$48-E2)") (class "Default")
      (node (ref "R39") (pin "1") (pinfunction "1_1") (pintype "passive"))
      (node (ref "U$48") (pin "3") (pinfunction "E2_3") (pintype "passive"))
    )
    (net (code "37") (name "Net-(U$49-B)") (class "Default")
      (node (ref "Q1") (pin "C") (pinfunction "C_C") (pintype "passive"))
      (node (ref "U$49") (pin "2") (pinfunction "B_2") (pintype "passive"))
      (node (ref "U$49") (pin "5") (pinfunction "C1_5") (pintype "passive"))
    )
    (net (code "38") (name "Net-(U$49-E1)") (class "Default")
      (node (ref "D22") (pin "C") (pinfunction "C_C") (pintype "passive"))
      (node (ref "U$49") (pin "1") (pinfunction "E1_1") (pintype "passive"))
    )
    (net (code "39") (name "Net-(U$49-E2)") (class "Default")
      (node (ref "R37") (pin "2") (pinfunction "2_2") (pintype "passive"))
      (node (ref "U$49") (pin "3") (pinfunction "E2_3") (pintype "passive"))
    )
    (net (code "40") (name "V+") (class "Default")
      (node (ref "C106") (pin "+") (pinfunction "+_+") (pintype "passive"))
      (node (ref "C108") (pin "1") (pinfunction "1_1") (pintype "passive"))
      (node (ref "C110") (pin "1") (pinfunction "1_1") (pintype "passive"))
      (node (ref "C112") (pin "1") (pinfunction "1_1") (pintype "passive"))
      (node (ref "C113") (pin "1") (pinfunction "1_1") (pintype "passive"))
      (node (ref "C114") (pin "1") (pinfunction "1_1") (pintype "passive"))
      (node (ref "C115") (pin "1") (pinfunction "1_1") (pintype "passive"))
      (node (ref "C120") (pin "1") (pinfunction "1_1") (pintype "passive"))
      (node (ref "C132") (pin "1") (pinfunction "1_1") (pintype "passive"))
      (node (ref "D27") (pin "A") (pinfunction "A_A") (pintype "passive"))
      (node (ref "IC10") (pin "2") (pinfunction "IN_2") (pintype "input"))
      (node (ref "IC11") (pin "7") (pinfunction "V+_7") (pintype "power_in"))
      (node (ref "R44") (pin "2") (pinfunction "2_2") (pintype "passive"))
      (node (ref "R46") (pin "2") (pinfunction "2_2") (pintype "passive"))
      (node (ref "R47") (pin "2") (pinfunction "2_2") (pintype "passive"))
      (node (ref "U$44") (pin "3") (pinfunction "E_3") (pintype "passive"))
      (node (ref "X2") (pin "1") (pinfunction "S_1") (pintype "passive"))
    )
    (net (code "41") (name "V-") (class "Default")
      (node (ref "C107") (pin "-") (pinfunction "-_-") (pintype "passive"))
      (node (ref "C109") (pin "2") (pinfunction "2_2") (pintype "passive"))
      (node (ref "C116") (pin "2") (pinfunction "2_2") (pintype "passive"))
      (node (ref "C117") (pin "2") (pinfunction "2_2") (pintype "passive"))
      (node (ref "C118") (pin "2") (pinfunction "2_2") (pintype "passive"))
      (node (ref "C119") (pin "2") (pinfunction "2_2") (pintype "passive"))
      (node (ref "C121") (pin "2") (pinfunction "2_2") (pintype "passive"))
      (node (ref "C130") (pin "2") (pinfunction "2_2") (pintype "passive"))
      (node (ref "D26") (pin "C") (pinfunction "C_C") (pintype "passive"))
      (node (ref "IC12") (pin "4") (pinfunction "V-_4") (pintype "power_in"))
      (node (ref "R45") (pin "1") (pinfunction "1_1") (pintype "passive"))
      (node (ref "R48") (pin "1") (pinfunction "1_1") (pintype "passive"))
      (node (ref "U$45") (pin "3") (pinfunction "E_3") (pintype "passive"))
      (node (ref "X2") (pin "3") (pinfunction "S_3") (pintype "passive"))
    )
    (net (code "42") (name "unconnected-(IC11-CMP1-Pad1)") (class "Default")
      (node (ref "IC11") (pin "1") (pinfunction "CMP1_1") (pintype "passive"))
    )
    (net (code "43") (name "unconnected-(IC11-CMP2-Pad8)") (class "Default")
      (node (ref "IC11") (pin "8") (pinfunction "CMP2_8") (pintype "passive"))
    )
    (net (code "44") (name "unconnected-(IC12-CMP1-Pad1)") (class "Default")
      (node (ref "IC12") (pin "1") (pinfunction "CMP1_1") (pintype "passive"))
    )
    (net (code "45") (name "unconnected-(IC12-CMP2-Pad8)") (class "Default")
      (node (ref "IC12") (pin "8") (pinfunction "CMP2_8") (pintype "passive"))
    )
  )
)
